# zucker_E77.net
KiCad netlist of a schematic drawn in Altium Designer
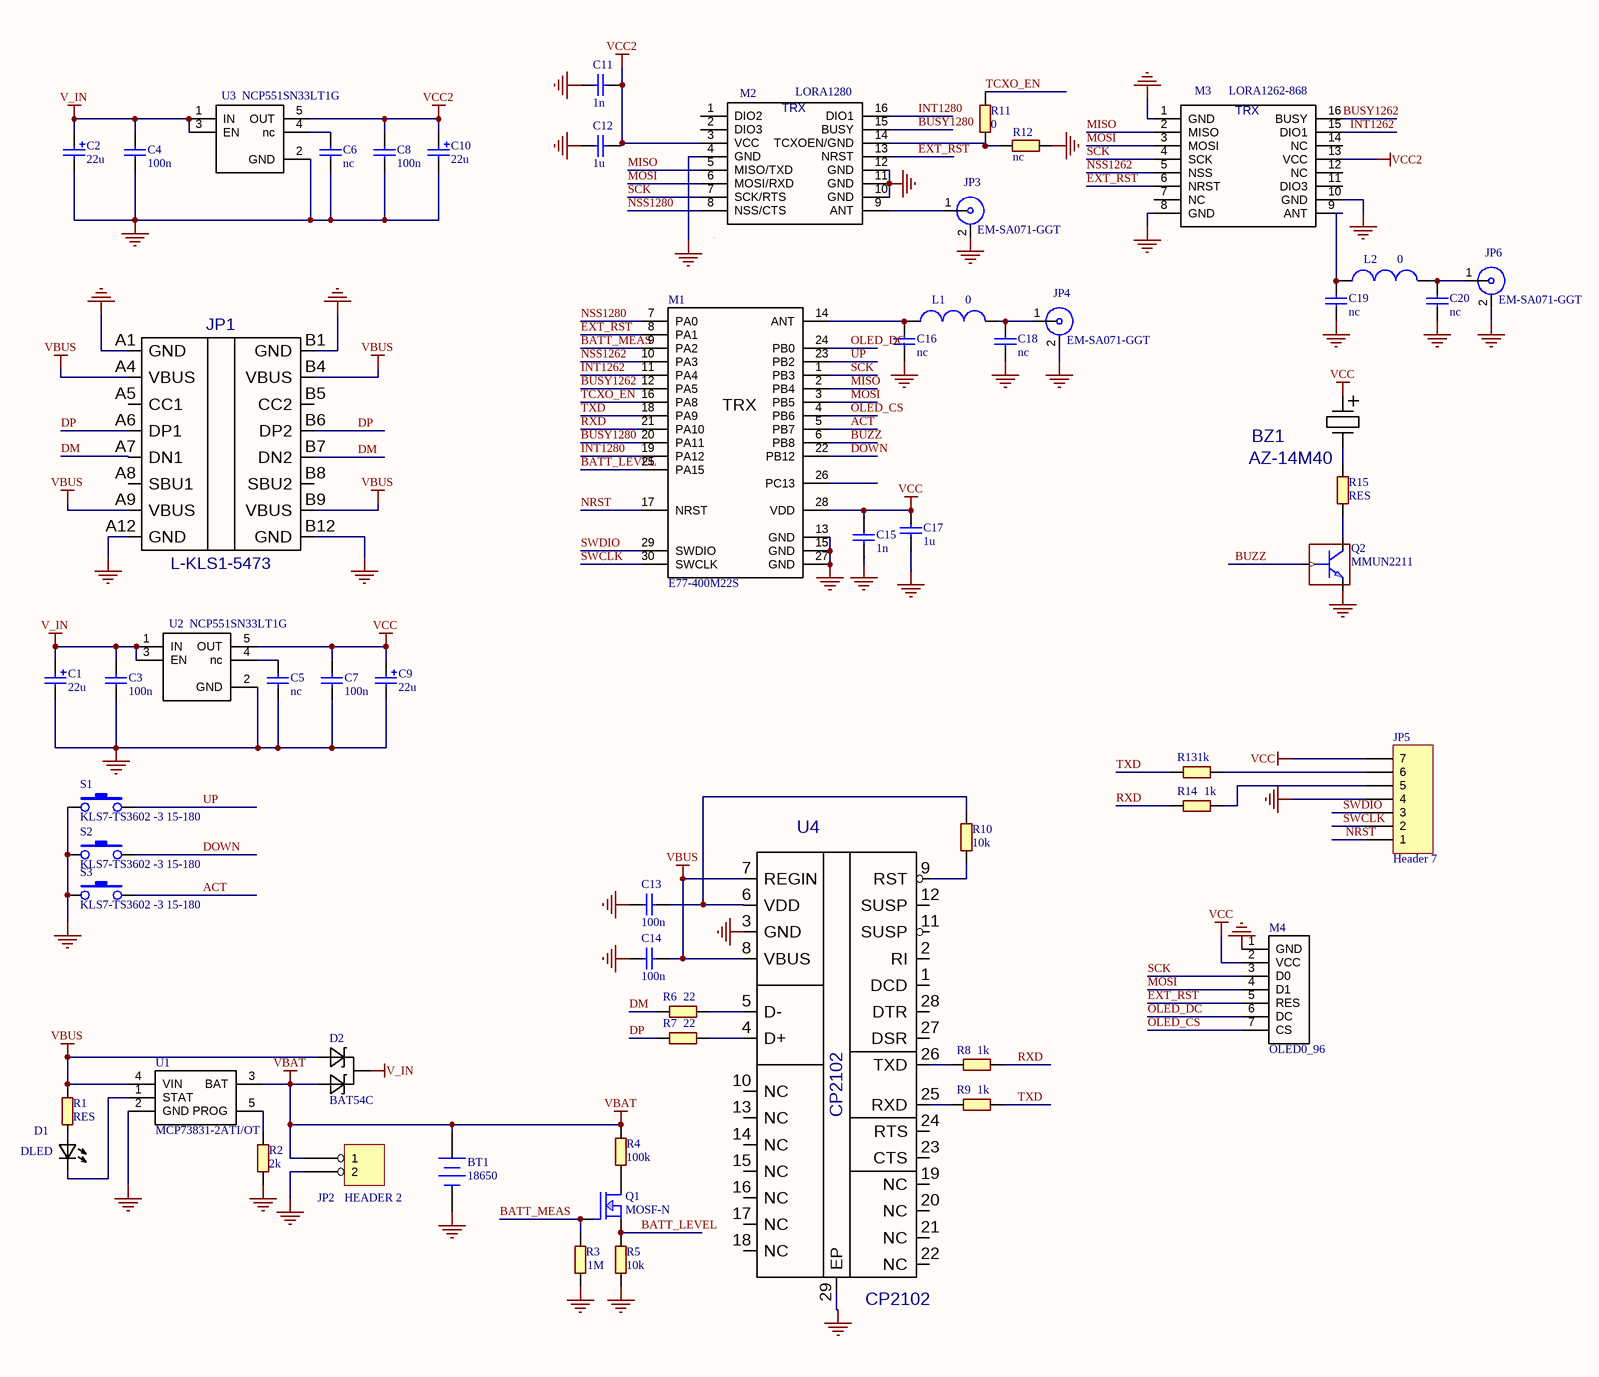
[diagram p0: zucker_E77.SchDoc]

(export (version "E")
  (design (tool "Eeschema 10.0.6"))
  (components
    (comp (ref "BT1")
      (value "18650")
      (footprint "18650")
      (description "Multicell Battery")
      (fields (field (name "PUBLISHER") "Altium Limited"))
      (libsource (lib "zucker") (part "Battery"))
    )
    (comp (ref "BZ1")
      (value "AZ-14M40")
      (footprint "AZ-14M40")
      (libsource (lib "zucker") (part "BUZ-AZ-14M40"))
    )
    (comp (ref "C1")
      (value "22u")
      (footprint "C_TANTAL_A")
      (fields (field (name "VOLTAGE") "16V"))
      (libsource (lib "Passive") (part "CAPP"))
    )
    (comp (ref "C2")
      (value "22u")
      (footprint "C_TANTAL_A")
      (fields (field (name "VOLTAGE") "16V"))
      (libsource (lib "Passive") (part "CAPP"))
    )
    (comp (ref "C3")
      (value "100n")
      (footprint "C-0603")
      (fields (field (name "VOLTAGE") "50V"))
      (libsource (lib "Passive") (part "CAPN"))
    )
    (comp (ref "C4")
      (value "100n")
      (footprint "C-0603")
      (fields (field (name "VOLTAGE") "50V"))
      (libsource (lib "Passive") (part "CAPN"))
    )
    (comp (ref "C5")
      (value "nc")
      (footprint "C-0603")
      (fields (field (name "VOLTAGE") "50V"))
      (libsource (lib "Passive") (part "CAPN"))
    )
    (comp (ref "C6")
      (value "nc")
      (footprint "C-0603")
      (fields (field (name "VOLTAGE") "50V"))
      (libsource (lib "Passive") (part "CAPN"))
    )
    (comp (ref "C7")
      (value "100n")
      (footprint "C-0603")
      (fields (field (name "VOLTAGE") "50V"))
      (libsource (lib "Passive") (part "CAPN"))
    )
    (comp (ref "C8")
      (value "100n")
      (footprint "C-0603")
      (fields (field (name "VOLTAGE") "50V"))
      (libsource (lib "Passive") (part "CAPN"))
    )
    (comp (ref "C9")
      (value "22u")
      (footprint "C_TANTAL_A")
      (fields (field (name "VOLTAGE") "16V"))
      (libsource (lib "Passive") (part "CAPP"))
    )
    (comp (ref "C10")
      (value "22u")
      (footprint "C_TANTAL_A")
      (fields (field (name "VOLTAGE") "16V"))
      (libsource (lib "Passive") (part "CAPP"))
    )
    (comp (ref "C11")
      (value "1n")
      (footprint "C-0603")
      (fields (field (name "VOLTAGE") "50V"))
      (libsource (lib "Passive") (part "CAPN"))
    )
    (comp (ref "C12")
      (value "1u")
      (footprint "C-0603")
      (fields (field (name "VOLTAGE") "50V"))
      (libsource (lib "Passive") (part "CAPN"))
    )
    (comp (ref "C13")
      (value "100n")
      (footprint "C-0603")
      (fields (field (name "VOLTAGE") "50V"))
      (libsource (lib "Passive") (part "CAPN"))
    )
    (comp (ref "C14")
      (value "100n")
      (footprint "C-0603")
      (fields (field (name "VOLTAGE") "50V"))
      (libsource (lib "Passive") (part "CAPN"))
    )
    (comp (ref "C15")
      (value "1n")
      (footprint "C-0603")
      (fields (field (name "VOLTAGE") "50V"))
      (libsource (lib "Passive") (part "CAPN"))
    )
    (comp (ref "C16")
      (value "nc")
      (footprint "C-0603")
      (fields (field (name "VOLTAGE") "50V"))
      (libsource (lib "Passive") (part "CAPN"))
    )
    (comp (ref "C17")
      (value "1u")
      (footprint "C-0603")
      (fields (field (name "VOLTAGE") "50V"))
      (libsource (lib "Passive") (part "CAPN"))
    )
    (comp (ref "C18")
      (value "nc")
      (footprint "C-0603")
      (fields (field (name "VOLTAGE") "50V"))
      (libsource (lib "Passive") (part "CAPN"))
    )
    (comp (ref "C19")
      (value "nc")
      (footprint "C-0603")
      (fields (field (name "VOLTAGE") "50V"))
      (libsource (lib "Passive") (part "CAPN"))
    )
    (comp (ref "C20")
      (value "nc")
      (footprint "C-0603")
      (fields (field (name "VOLTAGE") "50V"))
      (libsource (lib "Passive") (part "CAPN"))
    )
    (comp (ref "D1") (value "DLED") (footprint "LED_3mm_RED") (libsource (lib "zucker") (part "DLED")))
    (comp (ref "D2") (value "BAT54C") (footprint "SOT-23") (libsource (lib "zucker") (part "BAT54C")))
    (comp (ref "JP1")
      (value "L-KLS1-5473")
      (footprint "L-KLS1-5473")
      (libsource (lib "connectors") (part "L-KLS1-5473"))
    )
    (comp (ref "JP2")
      (value "HEADER 2")
      (footprint "PLS1-2")
      (libsource (lib "Connectors") (part "HEADER 2"))
    )
    (comp (ref "JP3")
      (value "EM-SA071-GGT")
      (footprint "SMA_F_EDGE")
      (description "SMA Female R/A PCB Mount")
      (libsource (lib "Connectors") (part "SMA"))
    )
    (comp (ref "JP4")
      (value "EM-SA071-GGT")
      (footprint "SMA_F_EDGE")
      (description "SMA Female R/A PCB Mount")
      (libsource (lib "Connectors") (part "SMA"))
    )
    (comp (ref "JP5")
      (value "Header 7")
      (footprint "PLS1-7R")
      (description "Header, 7-Pin")
      (fields (field (name "PUBLISHER") "Altium Limited"))
      (libsource (lib "Miscellaneous Connectors") (part "Header 7"))
    )
    (comp (ref "JP6")
      (value "EM-SA071-GGT")
      (footprint "SMA_F_EDGE")
      (description "SMA Female R/A PCB Mount")
      (libsource (lib "Connectors") (part "SMA"))
    )
    (comp (ref "L1") (value "0") (footprint "L-0603") (libsource (lib "Passive") (part "L")))
    (comp (ref "L2") (value "0") (footprint "L-0603") (libsource (lib "Passive") (part "L")))
    (comp (ref "M1")
      (value "E77-400M22S")
      (footprint "E77XX-M22")
      (libsource (lib "zucker") (part "E77-400M22S"))
    )
    (comp (ref "M2")
      (value "LORA1280")
      (footprint "LGA16_LORA1280")
      (libsource (lib "RA08T") (part "LORA1280"))
    )
    (comp (ref "M3")
      (value "LORA1262-868")
      (footprint "LGA16_LORA1280")
      (libsource (lib "zucker") (part "LORA1262"))
    )
    (comp (ref "M4") (value "OLED0_96") (footprint "OLED096") (libsource (lib "zucker") (part "OLED0_96")))
    (comp (ref "Q1") (value "MOSF-N") (footprint "SOT-23") (libsource (lib "Transistors") (part "MOSF-N")))
    (comp (ref "Q2")
      (value "MMUN2211")
      (footprint "SOT-23")
      (libsource (lib "Transistors") (part "MMUN2211"))
    )
    (comp (ref "R1") (value "RES") (footprint "R-0603") (libsource (lib "Passive") (part "RES")))
    (comp (ref "R2") (value "2k") (footprint "R-0603") (libsource (lib "") (part "RES_2")))
    (comp (ref "R3") (value "1M") (footprint "R-0603") (libsource (lib "Passive") (part "RES")))
    (comp (ref "R4") (value "100k") (footprint "R-0603") (libsource (lib "Passive") (part "RES")))
    (comp (ref "R5") (value "10k") (footprint "R-0603") (libsource (lib "Passive") (part "RES")))
    (comp (ref "R6") (value "22") (footprint "R-0603") (libsource (lib "") (part "RES_1")))
    (comp (ref "R7") (value "22") (footprint "R-0603") (libsource (lib "") (part "RES_1")))
    (comp (ref "R8") (value "1k") (footprint "R-0603") (libsource (lib "") (part "RES_1")))
    (comp (ref "R9") (value "1k") (footprint "R-0603") (libsource (lib "") (part "RES_1")))
    (comp (ref "R10") (value "10k") (footprint "R-0603") (libsource (lib "Passive") (part "RES")))
    (comp (ref "R11") (value "0") (footprint "R-0603") (libsource (lib "") (part "RES_2")))
    (comp (ref "R12") (value "nc") (footprint "R-0603") (libsource (lib "") (part "RES_3")))
    (comp (ref "R13") (value "1k") (footprint "R-0603") (libsource (lib "") (part "RES_1")))
    (comp (ref "R14") (value "1k") (footprint "R-0603") (libsource (lib "") (part "RES_1")))
    (comp (ref "R15") (value "RES") (footprint "R-0603") (libsource (lib "Passive") (part "RES")))
    (comp (ref "S1")
      (value "KLS7-TS3602 -3 15-180")
      (footprint "KLS7-TS3602")
      (libsource (lib "Switches") (part "SW-1"))
    )
    (comp (ref "S2")
      (value "KLS7-TS3602 -3 15-180")
      (footprint "KLS7-TS3602")
      (libsource (lib "Switches") (part "SW-1"))
    )
    (comp (ref "S3")
      (value "KLS7-TS3602 -3 15-180")
      (footprint "KLS7-TS3602")
      (libsource (lib "Switches") (part "SW-1"))
    )
    (comp (ref "U1")
      (value "MCP73831-2ATI/OT")
      (footprint "SOT-23-5")
      (libsource (lib "zucker") (part "MCP73831"))
    )
    (comp (ref "U2")
      (value "NCP551SN33LT1G")
      (footprint "SOT-23-5")
      (description "50mA Low-Dropout Regulator")
      (libsource (lib "zucker") (part "LP2980"))
    )
    (comp (ref "U3")
      (value "NCP551SN33LT1G")
      (footprint "SOT-23-5")
      (description "50mA Low-Dropout Regulator")
      (libsource (lib "zucker") (part "LP2980"))
    )
    (comp (ref "U4") (value "CP2102") (footprint "QFN28") (libsource (lib "E2002") (part "CP2102")))
  )
  (nets
    (net (code "1") (name "/ACT") (class "Default")
      (node (ref "M1") (pin "5") (pinfunction "PB7_5") (pintype "passive"))
      (node (ref "S3") (pin "2") (pinfunction "2_2") (pintype "passive"))
    )
    (net (code "2") (name "/BATT_LEVEL") (class "Default")
      (node (ref "M1") (pin "25") (pinfunction "PA15_25") (pintype "passive"))
      (node (ref "Q1") (pin "2") (pinfunction "SOURCE_2") (pintype "passive"))
      (node (ref "R5") (pin "1") (pinfunction "1_1") (pintype "passive"))
    )
    (net (code "3") (name "/BATT_MEAS") (class "Default")
      (node (ref "M1") (pin "9") (pinfunction "PA2_9") (pintype "passive"))
      (node (ref "Q1") (pin "1") (pinfunction "GATE_1") (pintype "passive"))
      (node (ref "R3") (pin "1") (pinfunction "1_1") (pintype "passive"))
    )
    (net (code "4") (name "/BUSY1262") (class "Default")
      (node (ref "M1") (pin "12") (pinfunction "PA5_12") (pintype "passive"))
      (node (ref "M3") (pin "16") (pinfunction "BUSY_16") (pintype "passive"))
    )
    (net (code "5") (name "/BUSY1280") (class "Default")
      (node (ref "M1") (pin "20") (pinfunction "PA11_20") (pintype "passive"))
      (node (ref "M2") (pin "15") (pinfunction "BUSY_15") (pintype "passive"))
    )
    (net (code "6") (name "/BUZZ") (class "Default")
      (node (ref "M1") (pin "6") (pinfunction "PB8_6") (pintype "passive"))
      (node (ref "Q2") (pin "1") (pinfunction "BASE_1") (pintype "input"))
    )
    (net (code "7") (name "/DM") (class "Default")
      (node (ref "JP1") (pin "A7") (pinfunction "DN1_A7") (pintype "passive"))
      (node (ref "JP1") (pin "B7") (pinfunction "DN2_B7") (pintype "passive"))
      (node (ref "R6") (pin "2") (pinfunction "2_2") (pintype "passive"))
    )
    (net (code "8") (name "/DOWN") (class "Default")
      (node (ref "M1") (pin "22") (pinfunction "PB12_22") (pintype "passive"))
      (node (ref "S2") (pin "2") (pinfunction "2_2") (pintype "passive"))
    )
    (net (code "9") (name "/DP") (class "Default")
      (node (ref "JP1") (pin "A6") (pinfunction "DP1_A6") (pintype "passive"))
      (node (ref "JP1") (pin "B6") (pinfunction "DP2_B6") (pintype "passive"))
      (node (ref "R7") (pin "2") (pinfunction "2_2") (pintype "passive"))
    )
    (net (code "10") (name "/EXT_RST") (class "Default")
      (node (ref "M1") (pin "8") (pinfunction "PA1_8") (pintype "passive"))
      (node (ref "M2") (pin "13") (pinfunction "NRST_13") (pintype "passive"))
      (node (ref "M3") (pin "6") (pinfunction "NRST_6") (pintype "passive"))
      (node (ref "M4") (pin "5") (pinfunction "RES_5") (pintype "passive"))
    )
    (net (code "11") (name "/INT1262") (class "Default")
      (node (ref "M1") (pin "11") (pinfunction "PA4_11") (pintype "passive"))
      (node (ref "M3") (pin "15") (pinfunction "DIO1_15") (pintype "passive"))
    )
    (net (code "12") (name "/INT1280") (class "Default")
      (node (ref "M1") (pin "19") (pinfunction "PA12_19") (pintype "passive"))
      (node (ref "M2") (pin "16") (pinfunction "DIO1_16") (pintype "passive"))
    )
    (net (code "13") (name "/MISO") (class "Default")
      (node (ref "M1") (pin "2") (pinfunction "PB4_2") (pintype "passive"))
      (node (ref "M2") (pin "5") (pinfunction "MISO/TXD_5") (pintype "passive"))
      (node (ref "M3") (pin "2") (pinfunction "MISO_2") (pintype "passive"))
    )
    (net (code "14") (name "/MOSI") (class "Default")
      (node (ref "M1") (pin "3") (pinfunction "PB5_3") (pintype "passive"))
      (node (ref "M2") (pin "6") (pinfunction "MOSI/RXD_6") (pintype "passive"))
      (node (ref "M3") (pin "3") (pinfunction "MOSI_3") (pintype "passive"))
      (node (ref "M4") (pin "4") (pinfunction "D1_4") (pintype "passive"))
    )
    (net (code "15") (name "/NRST") (class "Default")
      (node (ref "JP5") (pin "1") (pinfunction "1_1") (pintype "passive"))
      (node (ref "M1") (pin "17") (pinfunction "NRST_17") (pintype "passive"))
    )
    (net (code "16") (name "/NSS1262") (class "Default")
      (node (ref "M1") (pin "10") (pinfunction "PA3_10") (pintype "passive"))
      (node (ref "M3") (pin "5") (pinfunction "NSS_5") (pintype "passive"))
    )
    (net (code "17") (name "/NSS1280") (class "Default")
      (node (ref "M1") (pin "7") (pinfunction "PA0_7") (pintype "passive"))
      (node (ref "M2") (pin "8") (pinfunction "NSS/CTS_8") (pintype "passive"))
    )
    (net (code "18") (name "/OLED_CS") (class "Default")
      (node (ref "M1") (pin "4") (pinfunction "PB6_4") (pintype "passive"))
      (node (ref "M4") (pin "7") (pinfunction "CS_7") (pintype "passive"))
    )
    (net (code "19") (name "/OLED_DC") (class "Default")
      (node (ref "M1") (pin "24") (pinfunction "PB0_24") (pintype "passive"))
      (node (ref "M4") (pin "6") (pinfunction "DC_6") (pintype "passive"))
    )
    (net (code "20") (name "/RXD") (class "Default")
      (node (ref "M1") (pin "21") (pinfunction "PA10_21") (pintype "passive"))
      (node (ref "R14") (pin "2") (pinfunction "2_2") (pintype "passive"))
      (node (ref "R8") (pin "1") (pinfunction "1_1") (pintype "passive"))
    )
    (net (code "21") (name "/SCK") (class "Default")
      (node (ref "M1") (pin "1") (pinfunction "PB3_1") (pintype "passive"))
      (node (ref "M2") (pin "7") (pinfunction "SCK/RTS_7") (pintype "passive"))
      (node (ref "M3") (pin "4") (pinfunction "SCK_4") (pintype "passive"))
      (node (ref "M4") (pin "3") (pinfunction "D0_3") (pintype "passive"))
    )
    (net (code "22") (name "/SWCLK") (class "Default")
      (node (ref "JP5") (pin "2") (pinfunction "2_2") (pintype "passive"))
      (node (ref "M1") (pin "30") (pinfunction "SWCLK_30") (pintype "passive"))
    )
    (net (code "23") (name "/SWDIO") (class "Default")
      (node (ref "JP5") (pin "3") (pinfunction "3_3") (pintype "passive"))
      (node (ref "M1") (pin "29") (pinfunction "SWDIO_29") (pintype "passive"))
    )
    (net (code "24") (name "/TCXO_EN") (class "Default")
      (node (ref "M1") (pin "16") (pinfunction "PA8_16") (pintype "passive"))
      (node (ref "R11") (pin "2") (pinfunction "2_2") (pintype "passive"))
    )
    (net (code "25") (name "/TXD") (class "Default")
      (node (ref "M1") (pin "18") (pinfunction "PA9_18") (pintype "passive"))
      (node (ref "R13") (pin "2") (pinfunction "2_2") (pintype "passive"))
      (node (ref "R9") (pin "1") (pinfunction "1_1") (pintype "passive"))
    )
    (net (code "26") (name "/UP") (class "Default")
      (node (ref "M1") (pin "23") (pinfunction "PB2_23") (pintype "passive"))
      (node (ref "S1") (pin "2") (pinfunction "2_2") (pintype "passive"))
    )
    (net (code "27") (name "GND") (class "Default")
      (node (ref "BT1") (pin "2") (pinfunction "-_2") (pintype "passive"))
      (node (ref "C1") (pin "1") (pinfunction "1_1") (pintype "passive"))
      (node (ref "C10") (pin "1") (pinfunction "1_1") (pintype "passive"))
      (node (ref "C11") (pin "2") (pinfunction "2_2") (pintype "passive"))
      (node (ref "C12") (pin "2") (pinfunction "2_2") (pintype "passive"))
      (node (ref "C13") (pin "2") (pinfunction "2_2") (pintype "passive"))
      (node (ref "C14") (pin "1") (pinfunction "1_1") (pintype "passive"))
      (node (ref "C15") (pin "2") (pinfunction "2_2") (pintype "passive"))
      (node (ref "C16") (pin "2") (pinfunction "2_2") (pintype "passive"))
      (node (ref "C17") (pin "2") (pinfunction "2_2") (pintype "passive"))
      (node (ref "C18") (pin "2") (pinfunction "2_2") (pintype "passive"))
      (node (ref "C19") (pin "2") (pinfunction "2_2") (pintype "passive"))
      (node (ref "C2") (pin "1") (pinfunction "1_1") (pintype "passive"))
      (node (ref "C20") (pin "2") (pinfunction "2_2") (pintype "passive"))
      (node (ref "C3") (pin "2") (pinfunction "2_2") (pintype "passive"))
      (node (ref "C4") (pin "2") (pinfunction "2_2") (pintype "passive"))
      (node (ref "C5") (pin "2") (pinfunction "2_2") (pintype "passive"))
      (node (ref "C6") (pin "2") (pinfunction "2_2") (pintype "passive"))
      (node (ref "C7") (pin "2") (pinfunction "2_2") (pintype "passive"))
      (node (ref "C8") (pin "2") (pinfunction "2_2") (pintype "passive"))
      (node (ref "C9") (pin "1") (pinfunction "1_1") (pintype "passive"))
      (node (ref "JP1") (pin "A1") (pinfunction "GND_A1") (pintype "passive"))
      (node (ref "JP1") (pin "A12") (pinfunction "GND_A12") (pintype "passive"))
      (node (ref "JP1") (pin "B1") (pinfunction "GND_B1") (pintype "passive"))
      (node (ref "JP1") (pin "B12") (pinfunction "GND_B12") (pintype "passive"))
      (node (ref "JP2") (pin "2") (pinfunction "2_2") (pintype "passive"))
      (node (ref "JP3") (pin "2") (pinfunction "2_2") (pintype "passive"))
      (node (ref "JP4") (pin "2") (pinfunction "2_2") (pintype "passive"))
      (node (ref "JP5") (pin "4") (pinfunction "4_4") (pintype "passive"))
      (node (ref "JP6") (pin "2") (pinfunction "2_2") (pintype "passive"))
      (node (ref "M1") (pin "13") (pinfunction "GND_13") (pintype "passive"))
      (node (ref "M1") (pin "15") (pinfunction "GND_15") (pintype "passive"))
      (node (ref "M1") (pin "27") (pinfunction "GND_27") (pintype "passive"))
      (node (ref "M2") (pin "10") (pinfunction "GND_10") (pintype "passive"))
      (node (ref "M2") (pin "11") (pinfunction "GND_11") (pintype "passive"))
      (node (ref "M2") (pin "12") (pinfunction "GND_12") (pintype "passive"))
      (node (ref "M2") (pin "4") (pinfunction "GND_4") (pintype "passive"))
      (node (ref "M3") (pin "1") (pinfunction "GND_1") (pintype "passive"))
      (node (ref "M3") (pin "10") (pinfunction "GND_10") (pintype "passive"))
      (node (ref "M3") (pin "8") (pinfunction "GND_8") (pintype "passive"))
      (node (ref "M4") (pin "1") (pinfunction "GND_1") (pintype "passive"))
      (node (ref "Q2") (pin "2") (pinfunction "EMITTER_2") (pintype "passive"))
      (node (ref "R12") (pin "2") (pinfunction "2_2") (pintype "passive"))
      (node (ref "R2") (pin "1") (pinfunction "1_1") (pintype "passive"))
      (node (ref "R3") (pin "2") (pinfunction "2_2") (pintype "passive"))
      (node (ref "R5") (pin "2") (pinfunction "2_2") (pintype "passive"))
      (node (ref "S1") (pin "1") (pinfunction "1_1") (pintype "passive"))
      (node (ref "S2") (pin "1") (pinfunction "1_1") (pintype "passive"))
      (node (ref "S3") (pin "1") (pinfunction "1_1") (pintype "passive"))
      (node (ref "U1") (pin "2") (pinfunction "GND_2") (pintype "passive"))
      (node (ref "U2") (pin "2") (pinfunction "GND_2") (pintype "passive"))
      (node (ref "U3") (pin "2") (pinfunction "GND_2") (pintype "passive"))
      (node (ref "U4") (pin "29") (pinfunction "EP_29") (pintype "passive"))
      (node (ref "U4") (pin "3") (pinfunction "GND_3") (pintype "passive"))
    )
    (net (code "28") (name "Net-(BZ1-Pad2)") (class "Default")
      (node (ref "BZ1") (pin "2") (pinfunction "2_2") (pintype "passive"))
      (node (ref "R15") (pin "1") (pinfunction "1_1") (pintype "passive"))
    )
    (net (code "29") (name "Net-(C18-Pad1)") (class "Default")
      (node (ref "C18") (pin "1") (pinfunction "1_1") (pintype "passive"))
      (node (ref "JP4") (pin "1") (pinfunction "1_1") (pintype "passive"))
      (node (ref "L1") (pin "2") (pinfunction "2_2") (pintype "passive"))
    )
    (net (code "30") (name "Net-(C20-Pad1)") (class "Default")
      (node (ref "C20") (pin "1") (pinfunction "1_1") (pintype "passive"))
      (node (ref "JP6") (pin "1") (pinfunction "1_1") (pintype "passive"))
      (node (ref "L2") (pin "2") (pinfunction "2_2") (pintype "passive"))
    )
    (net (code "31") (name "Net-(D1-Pad1)") (class "Default")
      (node (ref "D1") (pin "1") (pinfunction "1_1") (pintype "passive"))
      (node (ref "R1") (pin "2") (pinfunction "2_2") (pintype "passive"))
    )
    (net (code "32") (name "Net-(JP5-Pad5)") (class "Default")
      (node (ref "JP5") (pin "5") (pinfunction "5_5") (pintype "passive"))
      (node (ref "R14") (pin "1") (pinfunction "1_1") (pintype "passive"))
    )
    (net (code "33") (name "Net-(JP5-Pad6)") (class "Default")
      (node (ref "JP5") (pin "6") (pinfunction "6_6") (pintype "passive"))
      (node (ref "R13") (pin "1") (pinfunction "1_1") (pintype "passive"))
    )
    (net (code "34") (name "Net-(M1-ANT)") (class "Default")
      (node (ref "C16") (pin "1") (pinfunction "1_1") (pintype "passive"))
      (node (ref "L1") (pin "1") (pinfunction "1_1") (pintype "passive"))
      (node (ref "M1") (pin "14") (pinfunction "ANT_14") (pintype "passive"))
    )
    (net (code "35") (name "Net-(M2-ANT)") (class "Default")
      (node (ref "JP3") (pin "1") (pinfunction "1_1") (pintype "passive"))
      (node (ref "M2") (pin "9") (pinfunction "ANT_9") (pintype "passive"))
    )
    (net (code "36") (name "Net-(M2-TCXOEN{slash}GND)") (class "Default")
      (node (ref "M2") (pin "14") (pinfunction "TCXOEN/GND_14") (pintype "passive"))
      (node (ref "R11") (pin "1") (pinfunction "1_1") (pintype "passive"))
      (node (ref "R12") (pin "1") (pinfunction "1_1") (pintype "passive"))
    )
    (net (code "37") (name "Net-(M3-ANT)") (class "Default")
      (node (ref "C19") (pin "1") (pinfunction "1_1") (pintype "passive"))
      (node (ref "L2") (pin "1") (pinfunction "1_1") (pintype "passive"))
      (node (ref "M3") (pin "9") (pinfunction "ANT_9") (pintype "passive"))
    )
    (net (code "38") (name "Net-(Q1-DRAIN)") (class "Default")
      (node (ref "Q1") (pin "3") (pinfunction "DRAIN_3") (pintype "passive"))
      (node (ref "R4") (pin "2") (pinfunction "2_2") (pintype "passive"))
    )
    (net (code "39") (name "Net-(Q2-COLLECTOR)") (class "Default")
      (node (ref "Q2") (pin "3") (pinfunction "COLLECTOR_3") (pintype "passive"))
      (node (ref "R15") (pin "2") (pinfunction "2_2") (pintype "passive"))
    )
    (net (code "40") (name "Net-(U1-PROG)") (class "Default")
      (node (ref "R2") (pin "2") (pinfunction "2_2") (pintype "passive"))
      (node (ref "U1") (pin "5") (pinfunction "PROG_5") (pintype "passive"))
    )
    (net (code "41") (name "Net-(U1-STAT)") (class "Default")
      (node (ref "D1") (pin "2") (pinfunction "2_2") (pintype "passive"))
      (node (ref "U1") (pin "1") (pinfunction "STAT_1") (pintype "passive"))
    )
    (net (code "42") (name "Net-(U2-nc)") (class "Default")
      (node (ref "C5") (pin "1") (pinfunction "1_1") (pintype "passive"))
      (node (ref "U2") (pin "4") (pinfunction "nc_4") (pintype "passive"))
    )
    (net (code "43") (name "Net-(U3-nc)") (class "Default")
      (node (ref "C6") (pin "1") (pinfunction "1_1") (pintype "passive"))
      (node (ref "U3") (pin "4") (pinfunction "nc_4") (pintype "passive"))
    )
    (net (code "44") (name "Net-(U4-D+)") (class "Default")
      (node (ref "R7") (pin "1") (pinfunction "1_1") (pintype "passive"))
      (node (ref "U4") (pin "4") (pinfunction "D+_4") (pintype "passive"))
    )
    (net (code "45") (name "Net-(U4-D-)") (class "Default")
      (node (ref "R6") (pin "1") (pinfunction "1_1") (pintype "passive"))
      (node (ref "U4") (pin "5") (pinfunction "D-_5") (pintype "passive"))
    )
    (net (code "46") (name "Net-(U4-RST)") (class "Default")
      (node (ref "R10") (pin "2") (pinfunction "2_2") (pintype "passive"))
      (node (ref "U4") (pin "9") (pinfunction "RST_9") (pintype "passive"))
    )
    (net (code "47") (name "Net-(U4-RXD)") (class "Default")
      (node (ref "R9") (pin "2") (pinfunction "2_2") (pintype "passive"))
      (node (ref "U4") (pin "25") (pinfunction "RXD_25") (pintype "passive"))
    )
    (net (code "48") (name "Net-(U4-TXD)") (class "Default")
      (node (ref "R8") (pin "2") (pinfunction "2_2") (pintype "passive"))
      (node (ref "U4") (pin "26") (pinfunction "TXD_26") (pintype "passive"))
    )
    (net (code "49") (name "Net-(U4-VDD)") (class "Default")
      (node (ref "C13") (pin "1") (pinfunction "1_1") (pintype "passive"))
      (node (ref "R10") (pin "1") (pinfunction "1_1") (pintype "passive"))
      (node (ref "U4") (pin "6") (pinfunction "VDD_6") (pintype "passive"))
    )
    (net (code "50") (name "VBAT") (class "Default")
      (node (ref "BT1") (pin "1") (pinfunction "+_1") (pintype "passive"))
      (node (ref "D2") (pin "1") (pinfunction "A1_1") (pintype "passive"))
      (node (ref "JP2") (pin "1") (pinfunction "1_1") (pintype "passive"))
      (node (ref "R4") (pin "1") (pinfunction "1_1") (pintype "passive"))
      (node (ref "U1") (pin "3") (pinfunction "BAT_3") (pintype "passive"))
    )
    (net (code "51") (name "VBUS") (class "Default")
      (node (ref "C14") (pin "2") (pinfunction "2_2") (pintype "passive"))
      (node (ref "D2") (pin "2") (pinfunction "A2_2") (pintype "passive"))
      (node (ref "JP1") (pin "A4") (pinfunction "VBUS_A4") (pintype "passive"))
      (node (ref "JP1") (pin "A9") (pinfunction "VBUS_A9") (pintype "passive"))
      (node (ref "JP1") (pin "B4") (pinfunction "VBUS_B4") (pintype "passive"))
      (node (ref "JP1") (pin "B9") (pinfunction "VBUS_B9") (pintype "passive"))
      (node (ref "R1") (pin "1") (pinfunction "1_1") (pintype "passive"))
      (node (ref "U1") (pin "4") (pinfunction "VIN_4") (pintype "passive"))
      (node (ref "U4") (pin "7") (pinfunction "REGIN_7") (pintype "passive"))
      (node (ref "U4") (pin "8") (pinfunction "VBUS_8") (pintype "passive"))
    )
    (net (code "52") (name "VCC") (class "Default")
      (node (ref "BZ1") (pin "1") (pinfunction "1_1") (pintype "passive"))
      (node (ref "C15") (pin "1") (pinfunction "1_1") (pintype "passive"))
      (node (ref "C17") (pin "1") (pinfunction "1_1") (pintype "passive"))
      (node (ref "C7") (pin "1") (pinfunction "1_1") (pintype "passive"))
      (node (ref "C9") (pin "2") (pinfunction "2_2") (pintype "passive"))
      (node (ref "JP5") (pin "7") (pinfunction "7_7") (pintype "passive"))
      (node (ref "M1") (pin "28") (pinfunction "VDD_28") (pintype "passive"))
      (node (ref "M4") (pin "2") (pinfunction "VCC_2") (pintype "passive"))
      (node (ref "U2") (pin "5") (pinfunction "OUT_5") (pintype "passive"))
    )
    (net (code "53") (name "VCC2") (class "Default")
      (node (ref "C10") (pin "2") (pinfunction "2_2") (pintype "passive"))
      (node (ref "C11") (pin "1") (pinfunction "1_1") (pintype "passive"))
      (node (ref "C12") (pin "1") (pinfunction "1_1") (pintype "passive"))
      (node (ref "C8") (pin "1") (pinfunction "1_1") (pintype "passive"))
      (node (ref "M2") (pin "3") (pinfunction "VCC_3") (pintype "passive"))
      (node (ref "M3") (pin "13") (pinfunction "VCC_13") (pintype "passive"))
      (node (ref "U3") (pin "5") (pinfunction "OUT_5") (pintype "passive"))
    )
    (net (code "54") (name "VSS") (class "Default")
      (node (ref "JP1") (pin "17") (pinfunction "VSS_17") (pintype "power_in"))
    )
    (net (code "55") (name "V_IN") (class "Default")
      (node (ref "C1") (pin "2") (pinfunction "2_2") (pintype "passive"))
      (node (ref "C2") (pin "2") (pinfunction "2_2") (pintype "passive"))
      (node (ref "C3") (pin "1") (pinfunction "1_1") (pintype "passive"))
      (node (ref "C4") (pin "1") (pinfunction "1_1") (pintype "passive"))
      (node (ref "D2") (pin "3") (pinfunction "C1C2_3") (pintype "passive"))
      (node (ref "U2") (pin "1") (pinfunction "IN_1") (pintype "passive"))
      (node (ref "U2") (pin "3") (pinfunction "EN_3") (pintype "passive"))
      (node (ref "U3") (pin "1") (pinfunction "IN_1") (pintype "passive"))
      (node (ref "U3") (pin "3") (pinfunction "EN_3") (pintype "passive"))
    )
    (net (code "56") (name "unconnected-(JP1-CC1-PadA5)") (class "Default")
      (node (ref "JP1") (pin "A5") (pinfunction "CC1_A5") (pintype "passive"))
    )
    (net (code "57") (name "unconnected-(JP1-CC2-PadB5)") (class "Default")
      (node (ref "JP1") (pin "B5") (pinfunction "CC2_B5") (pintype "passive"))
    )
    (net (code "58") (name "unconnected-(JP1-SBU1-PadA8)") (class "Default")
      (node (ref "JP1") (pin "A8") (pinfunction "SBU1_A8") (pintype "passive"))
    )
    (net (code "59") (name "unconnected-(JP1-SBU2-PadB8)") (class "Default")
      (node (ref "JP1") (pin "B8") (pinfunction "SBU2_B8") (pintype "passive"))
    )
    (net (code "60") (name "unconnected-(M1-PC13-Pad26)") (class "Default")
      (node (ref "M1") (pin "26") (pinfunction "PC13_26") (pintype "passive"))
    )
    (net (code "61") (name "unconnected-(M2-DIO2-Pad1)") (class "Default")
      (node (ref "M2") (pin "1") (pinfunction "DIO2_1") (pintype "passive"))
    )
    (net (code "62") (name "unconnected-(M2-DIO3-Pad2)") (class "Default")
      (node (ref "M2") (pin "2") (pinfunction "DIO3_2") (pintype "passive"))
    )
    (net (code "63") (name "unconnected-(M3-DIO3-Pad11)") (class "Default")
      (node (ref "M3") (pin "11") (pinfunction "DIO3_11") (pintype "passive"))
    )
    (net (code "64") (name "unconnected-(M3-NC-Pad7)") (class "Default")
      (node (ref "M3") (pin "7") (pinfunction "NC_7") (pintype "passive"))
    )
    (net (code "65") (name "unconnected-(M3-NC-Pad12)") (class "Default")
      (node (ref "M3") (pin "12") (pinfunction "NC_12") (pintype "passive"))
    )
    (net (code "66") (name "unconnected-(M3-NC-Pad14)") (class "Default")
      (node (ref "M3") (pin "14") (pinfunction "NC_14") (pintype "passive"))
    )
    (net (code "67") (name "unconnected-(U4-CTS-Pad23)") (class "Default")
      (node (ref "U4") (pin "23") (pinfunction "CTS_23") (pintype "passive"))
    )
    (net (code "68") (name "unconnected-(U4-DCD-Pad1)") (class "Default")
      (node (ref "U4") (pin "1") (pinfunction "DCD_1") (pintype "passive"))
    )
    (net (code "69") (name "unconnected-(U4-DSR-Pad27)") (class "Default")
      (node (ref "U4") (pin "27") (pinfunction "DSR_27") (pintype "passive"))
    )
    (net (code "70") (name "unconnected-(U4-DTR-Pad28)") (class "Default")
      (node (ref "U4") (pin "28") (pinfunction "DTR_28") (pintype "passive"))
    )
    (net (code "71") (name "unconnected-(U4-NC-Pad10)") (class "Default")
      (node (ref "U4") (pin "10") (pinfunction "NC_10") (pintype "passive"))
    )
    (net (code "72") (name "unconnected-(U4-NC-Pad13)") (class "Default")
      (node (ref "U4") (pin "13") (pinfunction "NC_13") (pintype "passive"))
    )
    (net (code "73") (name "unconnected-(U4-NC-Pad14)") (class "Default")
      (node (ref "U4") (pin "14") (pinfunction "NC_14") (pintype "passive"))
    )
    (net (code "74") (name "unconnected-(U4-NC-Pad15)") (class "Default")
      (node (ref "U4") (pin "15") (pinfunction "NC_15") (pintype "passive"))
    )
    (net (code "75") (name "unconnected-(U4-NC-Pad16)") (class "Default")
      (node (ref "U4") (pin "16") (pinfunction "NC_16") (pintype "passive"))
    )
    (net (code "76") (name "unconnected-(U4-NC-Pad17)") (class "Default")
      (node (ref "U4") (pin "17") (pinfunction "NC_17") (pintype "passive"))
    )
    (net (code "77") (name "unconnected-(U4-NC-Pad18)") (class "Default")
      (node (ref "U4") (pin "18") (pinfunction "NC_18") (pintype "passive"))
    )
    (net (code "78") (name "unconnected-(U4-NC-Pad19)") (class "Default")
      (node (ref "U4") (pin "19") (pinfunction "NC_19") (pintype "passive"))
    )
    (net (code "79") (name "unconnected-(U4-NC-Pad20)") (class "Default")
      (node (ref "U4") (pin "20") (pinfunction "NC_20") (pintype "passive"))
    )
    (net (code "80") (name "unconnected-(U4-NC-Pad21)") (class "Default")
      (node (ref "U4") (pin "21") (pinfunction "NC_21") (pintype "passive"))
    )
    (net (code "81") (name "unconnected-(U4-NC-Pad22)") (class "Default")
      (node (ref "U4") (pin "22") (pinfunction "NC_22") (pintype "passive"))
    )
    (net (code "82") (name "unconnected-(U4-RI-Pad2)") (class "Default")
      (node (ref "U4") (pin "2") (pinfunction "RI_2") (pintype "passive"))
    )
    (net (code "83") (name "unconnected-(U4-RTS-Pad24)") (class "Default")
      (node (ref "U4") (pin "24") (pinfunction "RTS_24") (pintype "passive"))
    )
    (net (code "84") (name "unconnected-(U4-SUSP-Pad11)") (class "Default")
      (node (ref "U4") (pin "11") (pinfunction "SUSP_11") (pintype "passive"))
    )
    (net (code "85") (name "unconnected-(U4-SUSP-Pad12)") (class "Default")
      (node (ref "U4") (pin "12") (pinfunction "SUSP_12") (pintype "passive"))
    )
  )
)
